# 02_XEM.net
KiCad netlist of a schematic drawn in Altium Designer
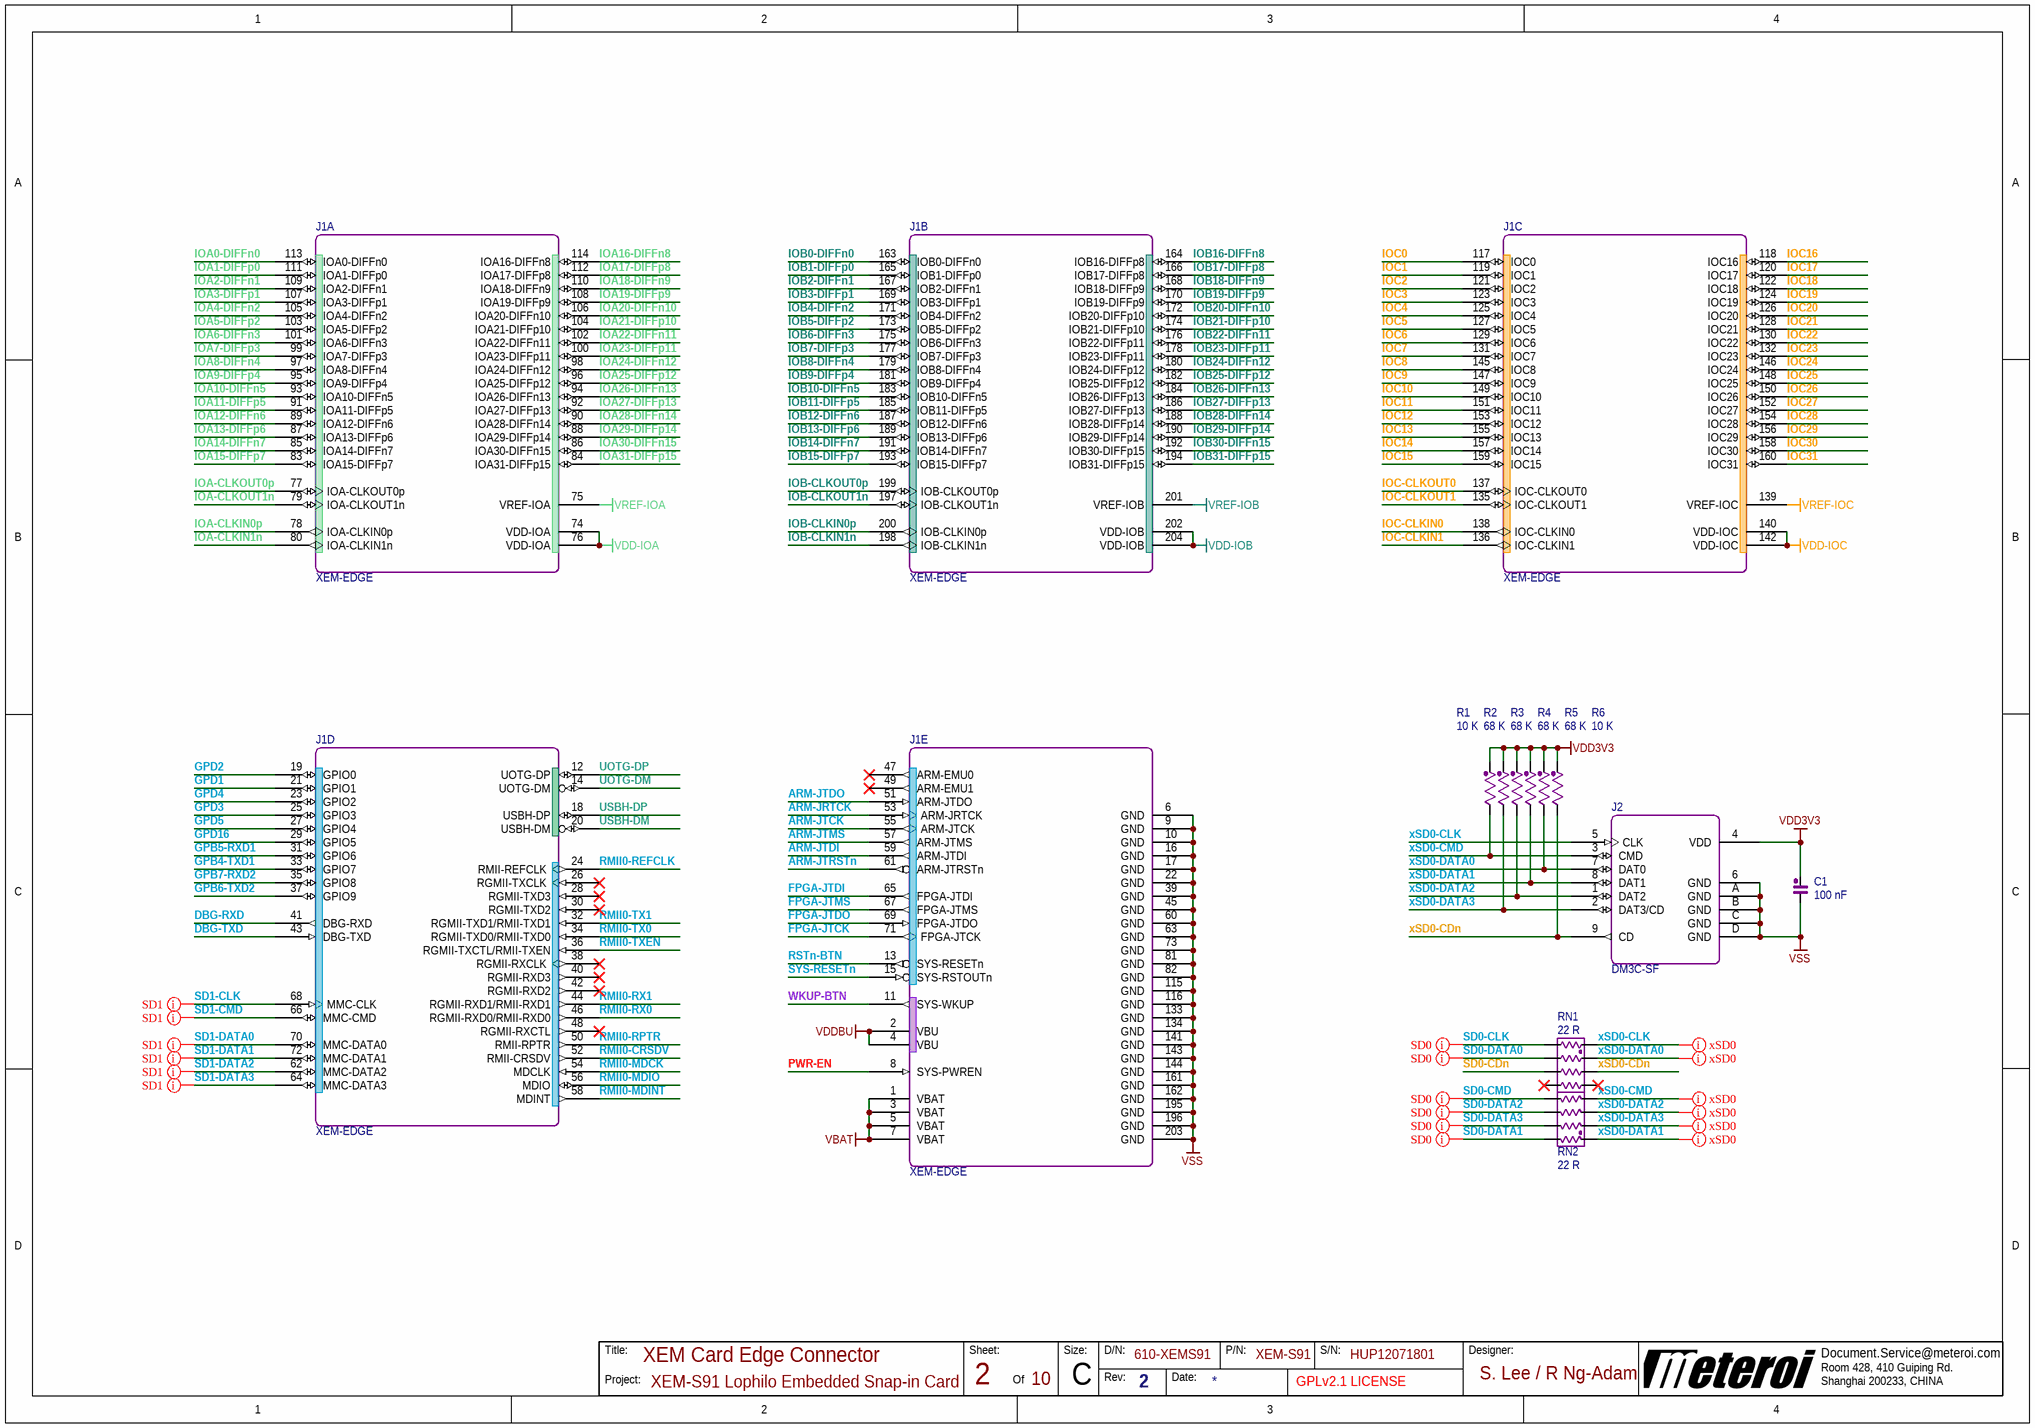
[diagram p0: 02_XEM.SchDoc]

(export (version "E")
  (design (tool "Eeschema 10.0.6"))
  (components
    (comp (ref "C1")
      (value "100 nF")
      (footprint "0402A1")
      (description "Normal Capacitor")
      (fields
        (field (name "PARTNUMBER") "0")
        (field (name "PUBLISHER") "Cowin")
        (field (name "DESIGNER") "shyul")
      )
      (libsource (lib "Basc_1_Passive") (part "CAP"))
    )
    (comp (ref "J1")
      (value "XEM-EDGE")
      (footprint "XEM-1C-204")
      (description "XEM Edge Connector 204-pins")
      (fields (field (name "PUBLISHER") "Cowin") (field (name "DESIGNER") "shyul"))
      (libsource (lib "PCB_XEM-S91") (part "XEM-EDGE"))
    )
    (comp (ref "J2")
      (value "DM3C-SF")
      (footprint "DM3C-SF")
      (description "Simple Switch 600mA Adjustable")
      (fields (field (name "PUBLISHER") "Cowin") (field (name "DESIGNER") "shyul"))
      (libsource (lib "PCB_XEM-S91") (part "DM3C-SF"))
    )
    (comp (ref "R1")
      (value "10 K")
      (footprint "0402A2")
      (description "Normal Resistor")
      (fields
        (field (name "PARTNUMBER") "0")
        (field (name "DESIGNER") "shyul")
        (field (name "PUBLISHER") "Cowin")
      )
      (libsource (lib "Basc_1_Passive") (part "RES"))
    )
    (comp (ref "R2")
      (value "68 K")
      (footprint "0402A2")
      (description "Normal Resistor")
      (fields
        (field (name "PARTNUMBER") "0")
        (field (name "DESIGNER") "shyul")
        (field (name "PUBLISHER") "Cowin")
      )
      (libsource (lib "Basc_1_Passive") (part "RES"))
    )
    (comp (ref "R3")
      (value "68 K")
      (footprint "0402A2")
      (description "Normal Resistor")
      (fields
        (field (name "PARTNUMBER") "0")
        (field (name "DESIGNER") "shyul")
        (field (name "PUBLISHER") "Cowin")
      )
      (libsource (lib "Basc_1_Passive") (part "RES"))
    )
    (comp (ref "R4")
      (value "68 K")
      (footprint "0402A2")
      (description "Normal Resistor")
      (fields
        (field (name "PARTNUMBER") "0")
        (field (name "DESIGNER") "shyul")
        (field (name "PUBLISHER") "Cowin")
      )
      (libsource (lib "Basc_1_Passive") (part "RES"))
    )
    (comp (ref "R5")
      (value "68 K")
      (footprint "0402A2")
      (description "Normal Resistor")
      (fields
        (field (name "PARTNUMBER") "0")
        (field (name "DESIGNER") "shyul")
        (field (name "PUBLISHER") "Cowin")
      )
      (libsource (lib "Basc_1_Passive") (part "RES"))
    )
    (comp (ref "R6")
      (value "10 K")
      (footprint "0402A2")
      (description "Normal Resistor")
      (fields
        (field (name "PARTNUMBER") "0")
        (field (name "DESIGNER") "shyul")
        (field (name "PUBLISHER") "Cowin")
      )
      (libsource (lib "Basc_1_Passive") (part "RES"))
    )
    (comp (ref "RN1")
      (value "22 R")
      (footprint "0402PR4")
      (description "Resistor Array x4")
      (fields
        (field (name "PARTNUMBER") "YC124-JR-0722RL")
        (field (name "PUBLISHER") "Cowin")
        (field (name "DESIGNER") "shyul")
      )
      (libsource (lib "Basc_1_Passive") (part "RES_N4"))
    )
    (comp (ref "RN2")
      (value "22 R")
      (footprint "0402PR4")
      (description "Resistor Array x4")
      (fields
        (field (name "PARTNUMBER") "YC124-JR-0722RL")
        (field (name "PUBLISHER") "Cowin")
        (field (name "DESIGNER") "shyul")
      )
      (libsource (lib "") (part "RES_N4_1"))
    )
  )
  (nets
    (net (code "1") (name "/ARM-JRTCK") (class "Default")
      (node (ref "J1") (pin "53") (pinfunction "ARM-JRTCK_53") (pintype "input"))
    )
    (net (code "2") (name "/ARM-JTCK") (class "Default")
      (node (ref "J1") (pin "55") (pinfunction "ARM-JTCK_55") (pintype "output"))
    )
    (net (code "3") (name "/ARM-JTDI") (class "Default")
      (node (ref "J1") (pin "59") (pinfunction "ARM-JTDI_59") (pintype "output"))
    )
    (net (code "4") (name "/ARM-JTDO") (class "Default")
      (node (ref "J1") (pin "51") (pinfunction "ARM-JTDO_51") (pintype "input"))
    )
    (net (code "5") (name "/ARM-JTMS") (class "Default")
      (node (ref "J1") (pin "57") (pinfunction "ARM-JTMS_57") (pintype "output"))
    )
    (net (code "6") (name "/ARM-JTRSTn") (class "Default")
      (node (ref "J1") (pin "61") (pinfunction "ARM-JTRSTn_61") (pintype "output"))
    )
    (net (code "7") (name "/DBG-RXD") (class "Default")
      (node (ref "J1") (pin "41") (pinfunction "DBG-RXD_41") (pintype "output"))
    )
    (net (code "8") (name "/DBG-TXD") (class "Default")
      (node (ref "J1") (pin "43") (pinfunction "DBG-TXD_43") (pintype "input"))
    )
    (net (code "9") (name "/FPGA-JTCK") (class "Default")
      (node (ref "J1") (pin "71") (pinfunction "FPGA-JTCK_71") (pintype "output"))
    )
    (net (code "10") (name "/FPGA-JTDI") (class "Default")
      (node (ref "J1") (pin "65") (pinfunction "FPGA-JTDI_65") (pintype "output"))
    )
    (net (code "11") (name "/FPGA-JTDO") (class "Default")
      (node (ref "J1") (pin "69") (pinfunction "FPGA-JTDO_69") (pintype "input"))
    )
    (net (code "12") (name "/FPGA-JTMS") (class "Default")
      (node (ref "J1") (pin "67") (pinfunction "FPGA-JTMS_67") (pintype "output"))
    )
    (net (code "13") (name "/GPB4-TXD1") (class "Default")
      (node (ref "J1") (pin "33") (pinfunction "GPIO7_33") (pintype "bidirectional"))
    )
    (net (code "14") (name "/GPB5-RXD1") (class "Default")
      (node (ref "J1") (pin "31") (pinfunction "GPIO6_31") (pintype "bidirectional"))
    )
    (net (code "15") (name "/GPB6-TXD2") (class "Default")
      (node (ref "J1") (pin "37") (pinfunction "GPIO9_37") (pintype "bidirectional"))
    )
    (net (code "16") (name "/GPB7-RXD2") (class "Default")
      (node (ref "J1") (pin "35") (pinfunction "GPIO8_35") (pintype "bidirectional"))
    )
    (net (code "17") (name "/GPD1") (class "Default")
      (node (ref "J1") (pin "21") (pinfunction "GPIO1_21") (pintype "bidirectional"))
    )
    (net (code "18") (name "/GPD2") (class "Default")
      (node (ref "J1") (pin "19") (pinfunction "GPIO0_19") (pintype "bidirectional"))
    )
    (net (code "19") (name "/GPD3") (class "Default")
      (node (ref "J1") (pin "25") (pinfunction "GPIO3_25") (pintype "bidirectional"))
    )
    (net (code "20") (name "/GPD4") (class "Default")
      (node (ref "J1") (pin "23") (pinfunction "GPIO2_23") (pintype "bidirectional"))
    )
    (net (code "21") (name "/GPD5") (class "Default")
      (node (ref "J1") (pin "27") (pinfunction "GPIO4_27") (pintype "bidirectional"))
    )
    (net (code "22") (name "/GPD16") (class "Default")
      (node (ref "J1") (pin "29") (pinfunction "GPIO5_29") (pintype "bidirectional"))
    )
    (net (code "23") (name "/IOA-CLKIN0p") (class "Default")
      (node (ref "J1") (pin "78") (pinfunction "IOA-CLKIN0p_78") (pintype "output"))
    )
    (net (code "24") (name "/IOA-CLKIN1n") (class "Default")
      (node (ref "J1") (pin "80") (pinfunction "IOA-CLKIN1n_80") (pintype "output"))
    )
    (net (code "25") (name "/IOA-CLKOUT0p") (class "Default")
      (node (ref "J1") (pin "77") (pinfunction "IOA-CLKOUT0p_77") (pintype "bidirectional"))
    )
    (net (code "26") (name "/IOA-CLKOUT1n") (class "Default")
      (node (ref "J1") (pin "79") (pinfunction "IOA-CLKOUT1n_79") (pintype "bidirectional"))
    )
    (net (code "27") (name "/IOA0-DIFFn0") (class "Default")
      (node (ref "J1") (pin "113") (pinfunction "IOA0-DIFFn0_113") (pintype "bidirectional"))
    )
    (net (code "28") (name "/IOA1-DIFFp0") (class "Default")
      (node (ref "J1") (pin "111") (pinfunction "IOA1-DIFFp0_111") (pintype "bidirectional"))
    )
    (net (code "29") (name "/IOA2-DIFFn1") (class "Default")
      (node (ref "J1") (pin "109") (pinfunction "IOA2-DIFFn1_109") (pintype "bidirectional"))
    )
    (net (code "30") (name "/IOA3-DIFFp1") (class "Default")
      (node (ref "J1") (pin "107") (pinfunction "IOA3-DIFFp1_107") (pintype "bidirectional"))
    )
    (net (code "31") (name "/IOA4-DIFFn2") (class "Default")
      (node (ref "J1") (pin "105") (pinfunction "IOA4-DIFFn2_105") (pintype "bidirectional"))
    )
    (net (code "32") (name "/IOA5-DIFFp2") (class "Default")
      (node (ref "J1") (pin "103") (pinfunction "IOA5-DIFFp2_103") (pintype "bidirectional"))
    )
    (net (code "33") (name "/IOA6-DIFFn3") (class "Default")
      (node (ref "J1") (pin "101") (pinfunction "IOA6-DIFFn3_101") (pintype "bidirectional"))
    )
    (net (code "34") (name "/IOA7-DIFFp3") (class "Default")
      (node (ref "J1") (pin "99") (pinfunction "IOA7-DIFFp3_99") (pintype "bidirectional"))
    )
    (net (code "35") (name "/IOA8-DIFFn4") (class "Default")
      (node (ref "J1") (pin "97") (pinfunction "IOA8-DIFFn4_97") (pintype "bidirectional"))
    )
    (net (code "36") (name "/IOA9-DIFFp4") (class "Default")
      (node (ref "J1") (pin "95") (pinfunction "IOA9-DIFFp4_95") (pintype "bidirectional"))
    )
    (net (code "37") (name "/IOA10-DIFFn5") (class "Default")
      (node (ref "J1") (pin "93") (pinfunction "IOA10-DIFFn5_93") (pintype "bidirectional"))
    )
    (net (code "38") (name "/IOA11-DIFFp5") (class "Default")
      (node (ref "J1") (pin "91") (pinfunction "IOA11-DIFFp5_91") (pintype "bidirectional"))
    )
    (net (code "39") (name "/IOA12-DIFFn6") (class "Default")
      (node (ref "J1") (pin "89") (pinfunction "IOA12-DIFFn6_89") (pintype "bidirectional"))
    )
    (net (code "40") (name "/IOA13-DIFFp6") (class "Default")
      (node (ref "J1") (pin "87") (pinfunction "IOA13-DIFFp6_87") (pintype "bidirectional"))
    )
    (net (code "41") (name "/IOA14-DIFFn7") (class "Default")
      (node (ref "J1") (pin "85") (pinfunction "IOA14-DIFFn7_85") (pintype "bidirectional"))
    )
    (net (code "42") (name "/IOA15-DIFFp7") (class "Default")
      (node (ref "J1") (pin "83") (pinfunction "IOA15-DIFFp7_83") (pintype "bidirectional"))
    )
    (net (code "43") (name "/IOA16-DIFFn8") (class "Default")
      (node (ref "J1") (pin "114") (pinfunction "IOA16-DIFFn8_114") (pintype "bidirectional"))
    )
    (net (code "44") (name "/IOA17-DIFFp8") (class "Default")
      (node (ref "J1") (pin "112") (pinfunction "IOA17-DIFFp8_112") (pintype "bidirectional"))
    )
    (net (code "45") (name "/IOA18-DIFFn9") (class "Default")
      (node (ref "J1") (pin "110") (pinfunction "IOA18-DIFFn9_110") (pintype "bidirectional"))
    )
    (net (code "46") (name "/IOA19-DIFFp9") (class "Default")
      (node (ref "J1") (pin "108") (pinfunction "IOA19-DIFFp9_108") (pintype "bidirectional"))
    )
    (net (code "47") (name "/IOA20-DIFFn10") (class "Default")
      (node (ref "J1") (pin "106") (pinfunction "IOA20-DIFFn10_106") (pintype "bidirectional"))
    )
    (net (code "48") (name "/IOA21-DIFFp10") (class "Default")
      (node (ref "J1") (pin "104") (pinfunction "IOA21-DIFFp10_104") (pintype "bidirectional"))
    )
    (net (code "49") (name "/IOA22-DIFFn11") (class "Default")
      (node (ref "J1") (pin "102") (pinfunction "IOA22-DIFFn11_102") (pintype "bidirectional"))
    )
    (net (code "50") (name "/IOA23-DIFFp11") (class "Default")
      (node (ref "J1") (pin "100") (pinfunction "IOA23-DIFFp11_100") (pintype "bidirectional"))
    )
    (net (code "51") (name "/IOA24-DIFFn12") (class "Default")
      (node (ref "J1") (pin "98") (pinfunction "IOA24-DIFFn12_98") (pintype "bidirectional"))
    )
    (net (code "52") (name "/IOA25-DIFFp12") (class "Default")
      (node (ref "J1") (pin "96") (pinfunction "IOA25-DIFFp12_96") (pintype "bidirectional"))
    )
    (net (code "53") (name "/IOA26-DIFFn13") (class "Default")
      (node (ref "J1") (pin "94") (pinfunction "IOA26-DIFFn13_94") (pintype "bidirectional"))
    )
    (net (code "54") (name "/IOA27-DIFFp13") (class "Default")
      (node (ref "J1") (pin "92") (pinfunction "IOA27-DIFFp13_92") (pintype "bidirectional"))
    )
    (net (code "55") (name "/IOA28-DIFFn14") (class "Default")
      (node (ref "J1") (pin "90") (pinfunction "IOA28-DIFFn14_90") (pintype "bidirectional"))
    )
    (net (code "56") (name "/IOA29-DIFFp14") (class "Default")
      (node (ref "J1") (pin "88") (pinfunction "IOA29-DIFFp14_88") (pintype "bidirectional"))
    )
    (net (code "57") (name "/IOA30-DIFFn15") (class "Default")
      (node (ref "J1") (pin "86") (pinfunction "IOA30-DIFFn15_86") (pintype "bidirectional"))
    )
    (net (code "58") (name "/IOA31-DIFFp15") (class "Default")
      (node (ref "J1") (pin "84") (pinfunction "IOA31-DIFFp15_84") (pintype "bidirectional"))
    )
    (net (code "59") (name "/IOB-CLKIN0p") (class "Default")
      (node (ref "J1") (pin "200") (pinfunction "IOB-CLKIN0p_200") (pintype "output"))
    )
    (net (code "60") (name "/IOB-CLKIN1n") (class "Default")
      (node (ref "J1") (pin "198") (pinfunction "IOB-CLKIN1n_198") (pintype "output"))
    )
    (net (code "61") (name "/IOB-CLKOUT0p") (class "Default")
      (node (ref "J1") (pin "199") (pinfunction "IOB-CLKOUT0p_199") (pintype "bidirectional"))
    )
    (net (code "62") (name "/IOB-CLKOUT1n") (class "Default")
      (node (ref "J1") (pin "197") (pinfunction "IOB-CLKOUT1n_197") (pintype "bidirectional"))
    )
    (net (code "63") (name "/IOB0-DIFFn0") (class "Default")
      (node (ref "J1") (pin "163") (pinfunction "IOB0-DIFFn0_163") (pintype "bidirectional"))
    )
    (net (code "64") (name "/IOB1-DIFFp0") (class "Default")
      (node (ref "J1") (pin "165") (pinfunction "IOB1-DIFFp0_165") (pintype "bidirectional"))
    )
    (net (code "65") (name "/IOB2-DIFFn1") (class "Default")
      (node (ref "J1") (pin "167") (pinfunction "IOB2-DIFFn1_167") (pintype "bidirectional"))
    )
    (net (code "66") (name "/IOB3-DIFFp1") (class "Default")
      (node (ref "J1") (pin "169") (pinfunction "IOB3-DIFFp1_169") (pintype "bidirectional"))
    )
    (net (code "67") (name "/IOB4-DIFFn2") (class "Default")
      (node (ref "J1") (pin "171") (pinfunction "IOB4-DIFFn2_171") (pintype "bidirectional"))
    )
    (net (code "68") (name "/IOB5-DIFFp2") (class "Default")
      (node (ref "J1") (pin "173") (pinfunction "IOB5-DIFFp2_173") (pintype "bidirectional"))
    )
    (net (code "69") (name "/IOB6-DIFFn3") (class "Default")
      (node (ref "J1") (pin "175") (pinfunction "IOB6-DIFFn3_175") (pintype "bidirectional"))
    )
    (net (code "70") (name "/IOB7-DIFFp3") (class "Default")
      (node (ref "J1") (pin "177") (pinfunction "IOB7-DIFFp3_177") (pintype "bidirectional"))
    )
    (net (code "71") (name "/IOB8-DIFFn4") (class "Default")
      (node (ref "J1") (pin "179") (pinfunction "IOB8-DIFFn4_179") (pintype "bidirectional"))
    )
    (net (code "72") (name "/IOB9-DIFFp4") (class "Default")
      (node (ref "J1") (pin "181") (pinfunction "IOB9-DIFFp4_181") (pintype "bidirectional"))
    )
    (net (code "73") (name "/IOB10-DIFFn5") (class "Default")
      (node (ref "J1") (pin "183") (pinfunction "IOB10-DIFFn5_183") (pintype "bidirectional"))
    )
    (net (code "74") (name "/IOB11-DIFFp5") (class "Default")
      (node (ref "J1") (pin "185") (pinfunction "IOB11-DIFFp5_185") (pintype "bidirectional"))
    )
    (net (code "75") (name "/IOB12-DIFFn6") (class "Default")
      (node (ref "J1") (pin "187") (pinfunction "IOB12-DIFFn6_187") (pintype "bidirectional"))
    )
    (net (code "76") (name "/IOB13-DIFFp6") (class "Default")
      (node (ref "J1") (pin "189") (pinfunction "IOB13-DIFFp6_189") (pintype "bidirectional"))
    )
    (net (code "77") (name "/IOB14-DIFFn7") (class "Default")
      (node (ref "J1") (pin "191") (pinfunction "IOB14-DIFFn7_191") (pintype "bidirectional"))
    )
    (net (code "78") (name "/IOB15-DIFFp7") (class "Default")
      (node (ref "J1") (pin "193") (pinfunction "IOB15-DIFFp7_193") (pintype "bidirectional"))
    )
    (net (code "79") (name "/IOB16-DIFFn8") (class "Default")
      (node (ref "J1") (pin "164") (pinfunction "IOB16-DIFFp8_164") (pintype "bidirectional"))
    )
    (net (code "80") (name "/IOB17-DIFFp8") (class "Default")
      (node (ref "J1") (pin "166") (pinfunction "IOB17-DIFFp8_166") (pintype "bidirectional"))
    )
    (net (code "81") (name "/IOB18-DIFFn9") (class "Default")
      (node (ref "J1") (pin "168") (pinfunction "IOB18-DIFFp9_168") (pintype "bidirectional"))
    )
    (net (code "82") (name "/IOB19-DIFFp9") (class "Default")
      (node (ref "J1") (pin "170") (pinfunction "IOB19-DIFFp9_170") (pintype "bidirectional"))
    )
    (net (code "83") (name "/IOB20-DIFFn10") (class "Default")
      (node (ref "J1") (pin "172") (pinfunction "IOB20-DIFFp10_172") (pintype "bidirectional"))
    )
    (net (code "84") (name "/IOB21-DIFFp10") (class "Default")
      (node (ref "J1") (pin "174") (pinfunction "IOB21-DIFFp10_174") (pintype "bidirectional"))
    )
    (net (code "85") (name "/IOB22-DIFFn11") (class "Default")
      (node (ref "J1") (pin "176") (pinfunction "IOB22-DIFFp11_176") (pintype "bidirectional"))
    )
    (net (code "86") (name "/IOB23-DIFFp11") (class "Default")
      (node (ref "J1") (pin "178") (pinfunction "IOB23-DIFFp11_178") (pintype "bidirectional"))
    )
    (net (code "87") (name "/IOB24-DIFFn12") (class "Default")
      (node (ref "J1") (pin "180") (pinfunction "IOB24-DIFFp12_180") (pintype "bidirectional"))
    )
    (net (code "88") (name "/IOB25-DIFFp12") (class "Default")
      (node (ref "J1") (pin "182") (pinfunction "IOB25-DIFFp12_182") (pintype "bidirectional"))
    )
    (net (code "89") (name "/IOB26-DIFFn13") (class "Default")
      (node (ref "J1") (pin "184") (pinfunction "IOB26-DIFFp13_184") (pintype "bidirectional"))
    )
    (net (code "90") (name "/IOB27-DIFFp13") (class "Default")
      (node (ref "J1") (pin "186") (pinfunction "IOB27-DIFFp13_186") (pintype "bidirectional"))
    )
    (net (code "91") (name "/IOB28-DIFFn14") (class "Default")
      (node (ref "J1") (pin "188") (pinfunction "IOB28-DIFFp14_188") (pintype "bidirectional"))
    )
    (net (code "92") (name "/IOB29-DIFFp14") (class "Default")
      (node (ref "J1") (pin "190") (pinfunction "IOB29-DIFFp14_190") (pintype "bidirectional"))
    )
    (net (code "93") (name "/IOB30-DIFFn15") (class "Default")
      (node (ref "J1") (pin "192") (pinfunction "IOB30-DIFFp15_192") (pintype "bidirectional"))
    )
    (net (code "94") (name "/IOB31-DIFFp15") (class "Default")
      (node (ref "J1") (pin "194") (pinfunction "IOB31-DIFFp15_194") (pintype "bidirectional"))
    )
    (net (code "95") (name "/IOC-CLKIN0") (class "Default")
      (node (ref "J1") (pin "138") (pinfunction "IOC-CLKIN0_138") (pintype "output"))
    )
    (net (code "96") (name "/IOC-CLKIN1") (class "Default")
      (node (ref "J1") (pin "136") (pinfunction "IOC-CLKIN1_136") (pintype "output"))
    )
    (net (code "97") (name "/IOC-CLKOUT0") (class "Default")
      (node (ref "J1") (pin "137") (pinfunction "IOC-CLKOUT0_137") (pintype "bidirectional"))
    )
    (net (code "98") (name "/IOC-CLKOUT1") (class "Default")
      (node (ref "J1") (pin "135") (pinfunction "IOC-CLKOUT1_135") (pintype "bidirectional"))
    )
    (net (code "99") (name "/IOC0") (class "Default")
      (node (ref "J1") (pin "117") (pinfunction "IOC0_117") (pintype "bidirectional"))
    )
    (net (code "100") (name "/IOC1") (class "Default")
      (node (ref "J1") (pin "119") (pinfunction "IOC1_119") (pintype "bidirectional"))
    )
    (net (code "101") (name "/IOC2") (class "Default")
      (node (ref "J1") (pin "121") (pinfunction "IOC2_121") (pintype "bidirectional"))
    )
    (net (code "102") (name "/IOC3") (class "Default")
      (node (ref "J1") (pin "123") (pinfunction "IOC3_123") (pintype "bidirectional"))
    )
    (net (code "103") (name "/IOC4") (class "Default")
      (node (ref "J1") (pin "125") (pinfunction "IOC4_125") (pintype "bidirectional"))
    )
    (net (code "104") (name "/IOC5") (class "Default")
      (node (ref "J1") (pin "127") (pinfunction "IOC5_127") (pintype "bidirectional"))
    )
    (net (code "105") (name "/IOC6") (class "Default")
      (node (ref "J1") (pin "129") (pinfunction "IOC6_129") (pintype "bidirectional"))
    )
    (net (code "106") (name "/IOC7") (class "Default")
      (node (ref "J1") (pin "131") (pinfunction "IOC7_131") (pintype "bidirectional"))
    )
    (net (code "107") (name "/IOC8") (class "Default")
      (node (ref "J1") (pin "145") (pinfunction "IOC8_145") (pintype "bidirectional"))
    )
    (net (code "108") (name "/IOC9") (class "Default")
      (node (ref "J1") (pin "147") (pinfunction "IOC9_147") (pintype "bidirectional"))
    )
    (net (code "109") (name "/IOC10") (class "Default")
      (node (ref "J1") (pin "149") (pinfunction "IOC10_149") (pintype "bidirectional"))
    )
    (net (code "110") (name "/IOC11") (class "Default")
      (node (ref "J1") (pin "151") (pinfunction "IOC11_151") (pintype "bidirectional"))
    )
    (net (code "111") (name "/IOC12") (class "Default")
      (node (ref "J1") (pin "153") (pinfunction "IOC12_153") (pintype "bidirectional"))
    )
    (net (code "112") (name "/IOC13") (class "Default")
      (node (ref "J1") (pin "155") (pinfunction "IOC13_155") (pintype "bidirectional"))
    )
    (net (code "113") (name "/IOC14") (class "Default")
      (node (ref "J1") (pin "157") (pinfunction "IOC14_157") (pintype "bidirectional"))
    )
    (net (code "114") (name "/IOC15") (class "Default")
      (node (ref "J1") (pin "159") (pinfunction "IOC15_159") (pintype "bidirectional"))
    )
    (net (code "115") (name "/IOC16") (class "Default")
      (node (ref "J1") (pin "118") (pinfunction "IOC16_118") (pintype "bidirectional"))
    )
    (net (code "116") (name "/IOC17") (class "Default")
      (node (ref "J1") (pin "120") (pinfunction "IOC17_120") (pintype "bidirectional"))
    )
    (net (code "117") (name "/IOC18") (class "Default")
      (node (ref "J1") (pin "122") (pinfunction "IOC18_122") (pintype "bidirectional"))
    )
    (net (code "118") (name "/IOC19") (class "Default")
      (node (ref "J1") (pin "124") (pinfunction "IOC19_124") (pintype "bidirectional"))
    )
    (net (code "119") (name "/IOC20") (class "Default")
      (node (ref "J1") (pin "126") (pinfunction "IOC20_126") (pintype "bidirectional"))
    )
    (net (code "120") (name "/IOC21") (class "Default")
      (node (ref "J1") (pin "128") (pinfunction "IOC21_128") (pintype "bidirectional"))
    )
    (net (code "121") (name "/IOC22") (class "Default")
      (node (ref "J1") (pin "130") (pinfunction "IOC22_130") (pintype "bidirectional"))
    )
    (net (code "122") (name "/IOC23") (class "Default")
      (node (ref "J1") (pin "132") (pinfunction "IOC23_132") (pintype "bidirectional"))
    )
    (net (code "123") (name "/IOC24") (class "Default")
      (node (ref "J1") (pin "146") (pinfunction "IOC24_146") (pintype "bidirectional"))
    )
    (net (code "124") (name "/IOC25") (class "Default")
      (node (ref "J1") (pin "148") (pinfunction "IOC25_148") (pintype "bidirectional"))
    )
    (net (code "125") (name "/IOC26") (class "Default")
      (node (ref "J1") (pin "150") (pinfunction "IOC26_150") (pintype "bidirectional"))
    )
    (net (code "126") (name "/IOC27") (class "Default")
      (node (ref "J1") (pin "152") (pinfunction "IOC27_152") (pintype "bidirectional"))
    )
    (net (code "127") (name "/IOC28") (class "Default")
      (node (ref "J1") (pin "154") (pinfunction "IOC28_154") (pintype "bidirectional"))
    )
    (net (code "128") (name "/IOC29") (class "Default")
      (node (ref "J1") (pin "156") (pinfunction "IOC29_156") (pintype "bidirectional"))
    )
    (net (code "129") (name "/IOC30") (class "Default")
      (node (ref "J1") (pin "158") (pinfunction "IOC30_158") (pintype "bidirectional"))
    )
    (net (code "130") (name "/IOC31") (class "Default")
      (node (ref "J1") (pin "160") (pinfunction "IOC31_160") (pintype "bidirectional"))
    )
    (net (code "131") (name "/PWR-EN") (class "Default")
      (node (ref "J1") (pin "8") (pinfunction "SYS-PWREN_8") (pintype "input"))
    )
    (net (code "132") (name "/RMII0-CRSDV") (class "Default")
      (node (ref "J1") (pin "52") (pinfunction "RMII-CRSDV_52") (pintype "output"))
    )
    (net (code "133") (name "/RMII0-MDCK") (class "Default")
      (node (ref "J1") (pin "54") (pinfunction "MDCLK_54") (pintype "input"))
    )
    (net (code "134") (name "/RMII0-MDINT") (class "Default")
      (node (ref "J1") (pin "58") (pinfunction "MDINT_58") (pintype "output"))
    )
    (net (code "135") (name "/RMII0-MDIO") (class "Default")
      (node (ref "J1") (pin "56") (pinfunction "MDIO_56") (pintype "bidirectional"))
    )
    (net (code "136") (name "/RMII0-REFCLK") (class "Default")
      (node (ref "J1") (pin "24") (pinfunction "RMII-REFCLK_24") (pintype "output"))
    )
    (net (code "137") (name "/RMII0-RPTR") (class "Default")
      (node (ref "J1") (pin "50") (pinfunction "RMII-RPTR_50") (pintype "output"))
    )
    (net (code "138") (name "/RMII0-RX0") (class "Default")
      (node (ref "J1") (pin "46") (pinfunction "RGMII-RXD0/RMII-RXD0_46") (pintype "output"))
    )
    (net (code "139") (name "/RMII0-RX1") (class "Default")
      (node (ref "J1") (pin "44") (pinfunction "RGMII-RXD1/RMII-RXD1_44") (pintype "output"))
    )
    (net (code "140") (name "/RMII0-TX0") (class "Default")
      (node (ref "J1") (pin "34") (pinfunction "RGMII-TXD0/RMII-TXD0_34") (pintype "input"))
    )
    (net (code "141") (name "/RMII0-TX1") (class "Default")
      (node (ref "J1") (pin "32") (pinfunction "RGMII-TXD1/RMII-TXD1_32") (pintype "input"))
    )
    (net (code "142") (name "/RMII0-TXEN") (class "Default")
      (node (ref "J1") (pin "36") (pinfunction "RGMII-TXCTL/RMII-TXEN_36") (pintype "input"))
    )
    (net (code "143") (name "/RSTn-BTN") (class "Default")
      (node (ref "J1") (pin "13") (pinfunction "SYS-RESETn_13") (pintype "output"))
    )
    (net (code "144") (name "/SD0-CDn") (class "Default")
      (node (ref "RN1") (pin "6") (pinfunction "6_6") (pintype "passive"))
    )
    (net (code "145") (name "/SD0-CLK") (class "Default")
      (node (ref "RN1") (pin "2") (pinfunction "2_2") (pintype "passive"))
    )
    (net (code "146") (name "/SD0-CMD") (class "Default")
      (node (ref "RN2") (pin "8") (pinfunction "8_8") (pintype "passive"))
    )
    (net (code "147") (name "/SD0-DATA0") (class "Default")
      (node (ref "RN1") (pin "4") (pinfunction "4_4") (pintype "passive"))
    )
    (net (code "148") (name "/SD0-DATA1") (class "Default")
      (node (ref "RN2") (pin "2") (pinfunction "2_2") (pintype "passive"))
    )
    (net (code "149") (name "/SD0-DATA2") (class "Default")
      (node (ref "RN2") (pin "6") (pinfunction "6_6") (pintype "passive"))
    )
    (net (code "150") (name "/SD0-DATA3") (class "Default")
      (node (ref "RN2") (pin "4") (pinfunction "4_4") (pintype "passive"))
    )
    (net (code "151") (name "/SD1-CLK") (class "Default")
      (node (ref "J1") (pin "68") (pinfunction "MMC-CLK_68") (pintype "input"))
    )
    (net (code "152") (name "/SD1-CMD") (class "Default")
      (node (ref "J1") (pin "66") (pinfunction "MMC-CMD_66") (pintype "bidirectional"))
    )
    (net (code "153") (name "/SD1-DATA0") (class "Default")
      (node (ref "J1") (pin "70") (pinfunction "MMC-DATA0_70") (pintype "bidirectional"))
    )
    (net (code "154") (name "/SD1-DATA1") (class "Default")
      (node (ref "J1") (pin "72") (pinfunction "MMC-DATA1_72") (pintype "bidirectional"))
    )
    (net (code "155") (name "/SD1-DATA2") (class "Default")
      (node (ref "J1") (pin "62") (pinfunction "MMC-DATA2_62") (pintype "bidirectional"))
    )
    (net (code "156") (name "/SD1-DATA3") (class "Default")
      (node (ref "J1") (pin "64") (pinfunction "MMC-DATA3_64") (pintype "bidirectional"))
    )
    (net (code "157") (name "/SYS-RESETn") (class "Default")
      (node (ref "J1") (pin "15") (pinfunction "SYS-RSTOUTn_15") (pintype "input"))
    )
    (net (code "158") (name "/UOTG-DM") (class "Default")
      (node (ref "J1") (pin "14") (pinfunction "UOTG-DM_14") (pintype "bidirectional"))
    )
    (net (code "159") (name "/UOTG-DP") (class "Default")
      (node (ref "J1") (pin "12") (pinfunction "UOTG-DP_12") (pintype "bidirectional"))
    )
    (net (code "160") (name "/USBH-DM") (class "Default")
      (node (ref "J1") (pin "20") (pinfunction "USBH-DM_20") (pintype "bidirectional"))
    )
    (net (code "161") (name "/USBH-DP") (class "Default")
      (node (ref "J1") (pin "18") (pinfunction "USBH-DP_18") (pintype "bidirectional"))
    )
    (net (code "162") (name "/WKUP-BTN") (class "Default")
      (node (ref "J1") (pin "11") (pinfunction "SYS-WKUP_11") (pintype "output"))
    )
    (net (code "163") (name "/xSD0-CDn") (class "Default")
      (node (ref "J2") (pin "9") (pinfunction "CD_9") (pintype "output"))
      (node (ref "R6") (pin "1") (pinfunction "1_1") (pintype "passive"))
      (node (ref "RN1") (pin "5") (pinfunction "5_5") (pintype "passive"))
    )
    (net (code "164") (name "/xSD0-CLK") (class "Default")
      (node (ref "J2") (pin "5") (pinfunction "CLK_5") (pintype "input"))
      (node (ref "RN1") (pin "1") (pinfunction "1_1") (pintype "passive"))
    )
    (net (code "165") (name "/xSD0-CMD") (class "Default")
      (node (ref "J2") (pin "3") (pinfunction "CMD_3") (pintype "bidirectional"))
      (node (ref "R1") (pin "1") (pinfunction "1_1") (pintype "passive"))
      (node (ref "RN2") (pin "7") (pinfunction "7_7") (pintype "passive"))
    )
    (net (code "166") (name "/xSD0-DATA0") (class "Default")
      (node (ref "J2") (pin "7") (pinfunction "DAT0_7") (pintype "bidirectional"))
      (node (ref "R5") (pin "1") (pinfunction "1_1") (pintype "passive"))
      (node (ref "RN1") (pin "3") (pinfunction "3_3") (pintype "passive"))
    )
    (net (code "167") (name "/xSD0-DATA1") (class "Default")
      (node (ref "J2") (pin "8") (pinfunction "DAT1_8") (pintype "bidirectional"))
      (node (ref "R4") (pin "1") (pinfunction "1_1") (pintype "passive"))
      (node (ref "RN2") (pin "1") (pinfunction "1_1") (pintype "passive"))
    )
    (net (code "168") (name "/xSD0-DATA2") (class "Default")
      (node (ref "J2") (pin "1") (pinfunction "DAT2_1") (pintype "bidirectional"))
      (node (ref "R3") (pin "1") (pinfunction "1_1") (pintype "passive"))
      (node (ref "RN2") (pin "5") (pinfunction "5_5") (pintype "passive"))
    )
    (net (code "169") (name "/xSD0-DATA3") (class "Default")
      (node (ref "J2") (pin "2") (pinfunction "DAT3/CD_2") (pintype "bidirectional"))
      (node (ref "R2") (pin "1") (pinfunction "1_1") (pintype "passive"))
      (node (ref "RN2") (pin "3") (pinfunction "3_3") (pintype "passive"))
    )
    (net (code "170") (name "VBAT") (class "Default")
      (node (ref "J1") (pin "1") (pinfunction "VBAT_1") (pintype "power_in"))
      (node (ref "J1") (pin "3") (pinfunction "VBAT_3") (pintype "power_in"))
      (node (ref "J1") (pin "5") (pinfunction "VBAT_5") (pintype "power_in"))
      (node (ref "J1") (pin "7") (pinfunction "VBAT_7") (pintype "power_in"))
    )
    (net (code "171") (name "VDD-IOA") (class "Default")
      (node (ref "J1") (pin "74") (pinfunction "VDD-IOA_74") (pintype "power_in"))
      (node (ref "J1") (pin "76") (pinfunction "VDD-IOA_76") (pintype "power_in"))
    )
    (net (code "172") (name "VDD-IOB") (class "Default")
      (node (ref "J1") (pin "202") (pinfunction "VDD-IOB_202") (pintype "power_in"))
      (node (ref "J1") (pin "204") (pinfunction "VDD-IOB_204") (pintype "power_in"))
    )
    (net (code "173") (name "VDD-IOC") (class "Default")
      (node (ref "J1") (pin "140") (pinfunction "VDD-IOC_140") (pintype "power_in"))
      (node (ref "J1") (pin "142") (pinfunction "VDD-IOC_142") (pintype "power_in"))
    )
    (net (code "174") (name "VDD3V3") (class "Default")
      (node (ref "C1") (pin "2") (pinfunction "2_2") (pintype "passive"))
      (node (ref "J2") (pin "4") (pinfunction "VDD_4") (pintype "passive"))
      (node (ref "R1") (pin "2") (pinfunction "2_2") (pintype "passive"))
      (node (ref "R2") (pin "2") (pinfunction "2_2") (pintype "passive"))
      (node (ref "R3") (pin "2") (pinfunction "2_2") (pintype "passive"))
      (node (ref "R4") (pin "2") (pinfunction "2_2") (pintype "passive"))
      (node (ref "R5") (pin "2") (pinfunction "2_2") (pintype "passive"))
      (node (ref "R6") (pin "2") (pinfunction "2_2") (pintype "passive"))
    )
    (net (code "175") (name "VDDBU") (class "Default")
      (node (ref "J1") (pin "2") (pinfunction "VBU_2") (pintype "power_in"))
      (node (ref "J1") (pin "4") (pinfunction "VBU_4") (pintype "power_in"))
    )
    (net (code "176") (name "VREF-IOA") (class "Default")
      (node (ref "J1") (pin "75") (pinfunction "VREF-IOA_75") (pintype "power_in"))
    )
    (net (code "177") (name "VREF-IOB") (class "Default")
      (node (ref "J1") (pin "201") (pinfunction "VREF-IOB_201") (pintype "power_in"))
    )
    (net (code "178") (name "VREF-IOC") (class "Default")
      (node (ref "J1") (pin "139") (pinfunction "VREF-IOC_139") (pintype "power_in"))
    )
    (net (code "179") (name "VSS") (class "Default")
      (node (ref "C1") (pin "1") (pinfunction "1_1") (pintype "passive"))
      (node (ref "J1") (pin "10") (pinfunction "GND_10") (pintype "passive"))
      (node (ref "J1") (pin "115") (pinfunction "GND_115") (pintype "passive"))
      (node (ref "J1") (pin "116") (pinfunction "GND_116") (pintype "passive"))
      (node (ref "J1") (pin "133") (pinfunction "GND_133") (pintype "passive"))
      (node (ref "J1") (pin "134") (pinfunction "GND_134") (pintype "passive"))
      (node (ref "J1") (pin "141") (pinfunction "GND_141") (pintype "passive"))
      (node (ref "J1") (pin "143") (pinfunction "GND_143") (pintype "passive"))
      (node (ref "J1") (pin "144") (pinfunction "GND_144") (pintype "passive"))
      (node (ref "J1") (pin "16") (pinfunction "GND_16") (pintype "passive"))
      (node (ref "J1") (pin "161") (pinfunction "GND_161") (pintype "passive"))
      (node (ref "J1") (pin "162") (pinfunction "GND_162") (pintype "passive"))
      (node (ref "J1") (pin "17") (pinfunction "GND_17") (pintype "passive"))
      (node (ref "J1") (pin "195") (pinfunction "GND_195") (pintype "passive"))
      (node (ref "J1") (pin "196") (pinfunction "GND_196") (pintype "passive"))
      (node (ref "J1") (pin "203") (pinfunction "GND_203") (pintype "passive"))
      (node (ref "J1") (pin "22") (pinfunction "GND_22") (pintype "passive"))
      (node (ref "J1") (pin "39") (pinfunction "GND_39") (pintype "passive"))
      (node (ref "J1") (pin "45") (pinfunction "GND_45") (pintype "passive"))
      (node (ref "J1") (pin "6") (pinfunction "GND_6") (pintype "passive"))
      (node (ref "J1") (pin "60") (pinfunction "GND_60") (pintype "passive"))
      (node (ref "J1") (pin "63") (pinfunction "GND_63") (pintype "passive"))
      (node (ref "J1") (pin "73") (pinfunction "GND_73") (pintype "passive"))
      (node (ref "J1") (pin "81") (pinfunction "GND_81") (pintype "passive"))
      (node (ref "J1") (pin "82") (pinfunction "GND_82") (pintype "passive"))
      (node (ref "J1") (pin "9") (pinfunction "GND_9") (pintype "passive"))
      (node (ref "J2") (pin "6") (pinfunction "GND_6") (pintype "passive"))
      (node (ref "J2") (pin "A") (pinfunction "GND_A") (pintype "passive"))
      (node (ref "J2") (pin "B") (pinfunction "GND_B") (pintype "passive"))
      (node (ref "J2") (pin "C") (pinfunction "GND_C") (pintype "passive"))
      (node (ref "J2") (pin "D") (pinfunction "GND_D") (pintype "passive"))
    )
    (net (code "180") (name "unconnected-(J1D-RGMII-RXCLK-Pad38)") (class "Default")
      (node (ref "J1") (pin "38") (pinfunction "RGMII-RXCLK_38") (pintype "output+no_connect"))
    )
    (net (code "181") (name "unconnected-(J1D-RGMII-RXCTL-Pad48)") (class "Default")
      (node (ref "J1") (pin "48") (pinfunction "RGMII-RXCTL_48") (pintype "output+no_connect"))
    )
    (net (code "182") (name "unconnected-(J1D-RGMII-RXD2-Pad42)") (class "Default")
      (node (ref "J1") (pin "42") (pinfunction "RGMII-RXD2_42") (pintype "output+no_connect"))
    )
    (net (code "183") (name "unconnected-(J1D-RGMII-RXD3-Pad40)") (class "Default")
      (node (ref "J1") (pin "40") (pinfunction "RGMII-RXD3_40") (pintype "output+no_connect"))
    )
    (net (code "184") (name "unconnected-(J1D-RGMII-TXCLK-Pad26)") (class "Default")
      (node (ref "J1") (pin "26") (pinfunction "RGMII-TXCLK_26") (pintype "input+no_connect"))
    )
    (net (code "185") (name "unconnected-(J1D-RGMII-TXD2-Pad30)") (class "Default")
      (node (ref "J1") (pin "30") (pinfunction "RGMII-TXD2_30") (pintype "input+no_connect"))
    )
    (net (code "186") (name "unconnected-(J1D-RGMII-TXD3-Pad28)") (class "Default")
      (node (ref "J1") (pin "28") (pinfunction "RGMII-TXD3_28") (pintype "input+no_connect"))
    )
    (net (code "187") (name "unconnected-(J1E-ARM-EMU0-Pad47)") (class "Default")
      (node (ref "J1") (pin "47") (pinfunction "ARM-EMU0_47") (pintype "output+no_connect"))
    )
    (net (code "188") (name "unconnected-(J1E-ARM-EMU1-Pad49)") (class "Default")
      (node (ref "J1") (pin "49") (pinfunction "ARM-EMU1_49") (pintype "output+no_connect"))
    )
    (net (code "189") (name "unconnected-(RN1-Pad7)") (class "Default")
      (node (ref "RN1") (pin "7") (pinfunction "7_7") (pintype "passive+no_connect"))
    )
    (net (code "190") (name "unconnected-(RN1-Pad8)") (class "Default")
      (node (ref "RN1") (pin "8") (pinfunction "8_8") (pintype "passive+no_connect"))
    )
  )
)
